# R123X.net
KiCad netlist of a schematic drawn in EAGLE
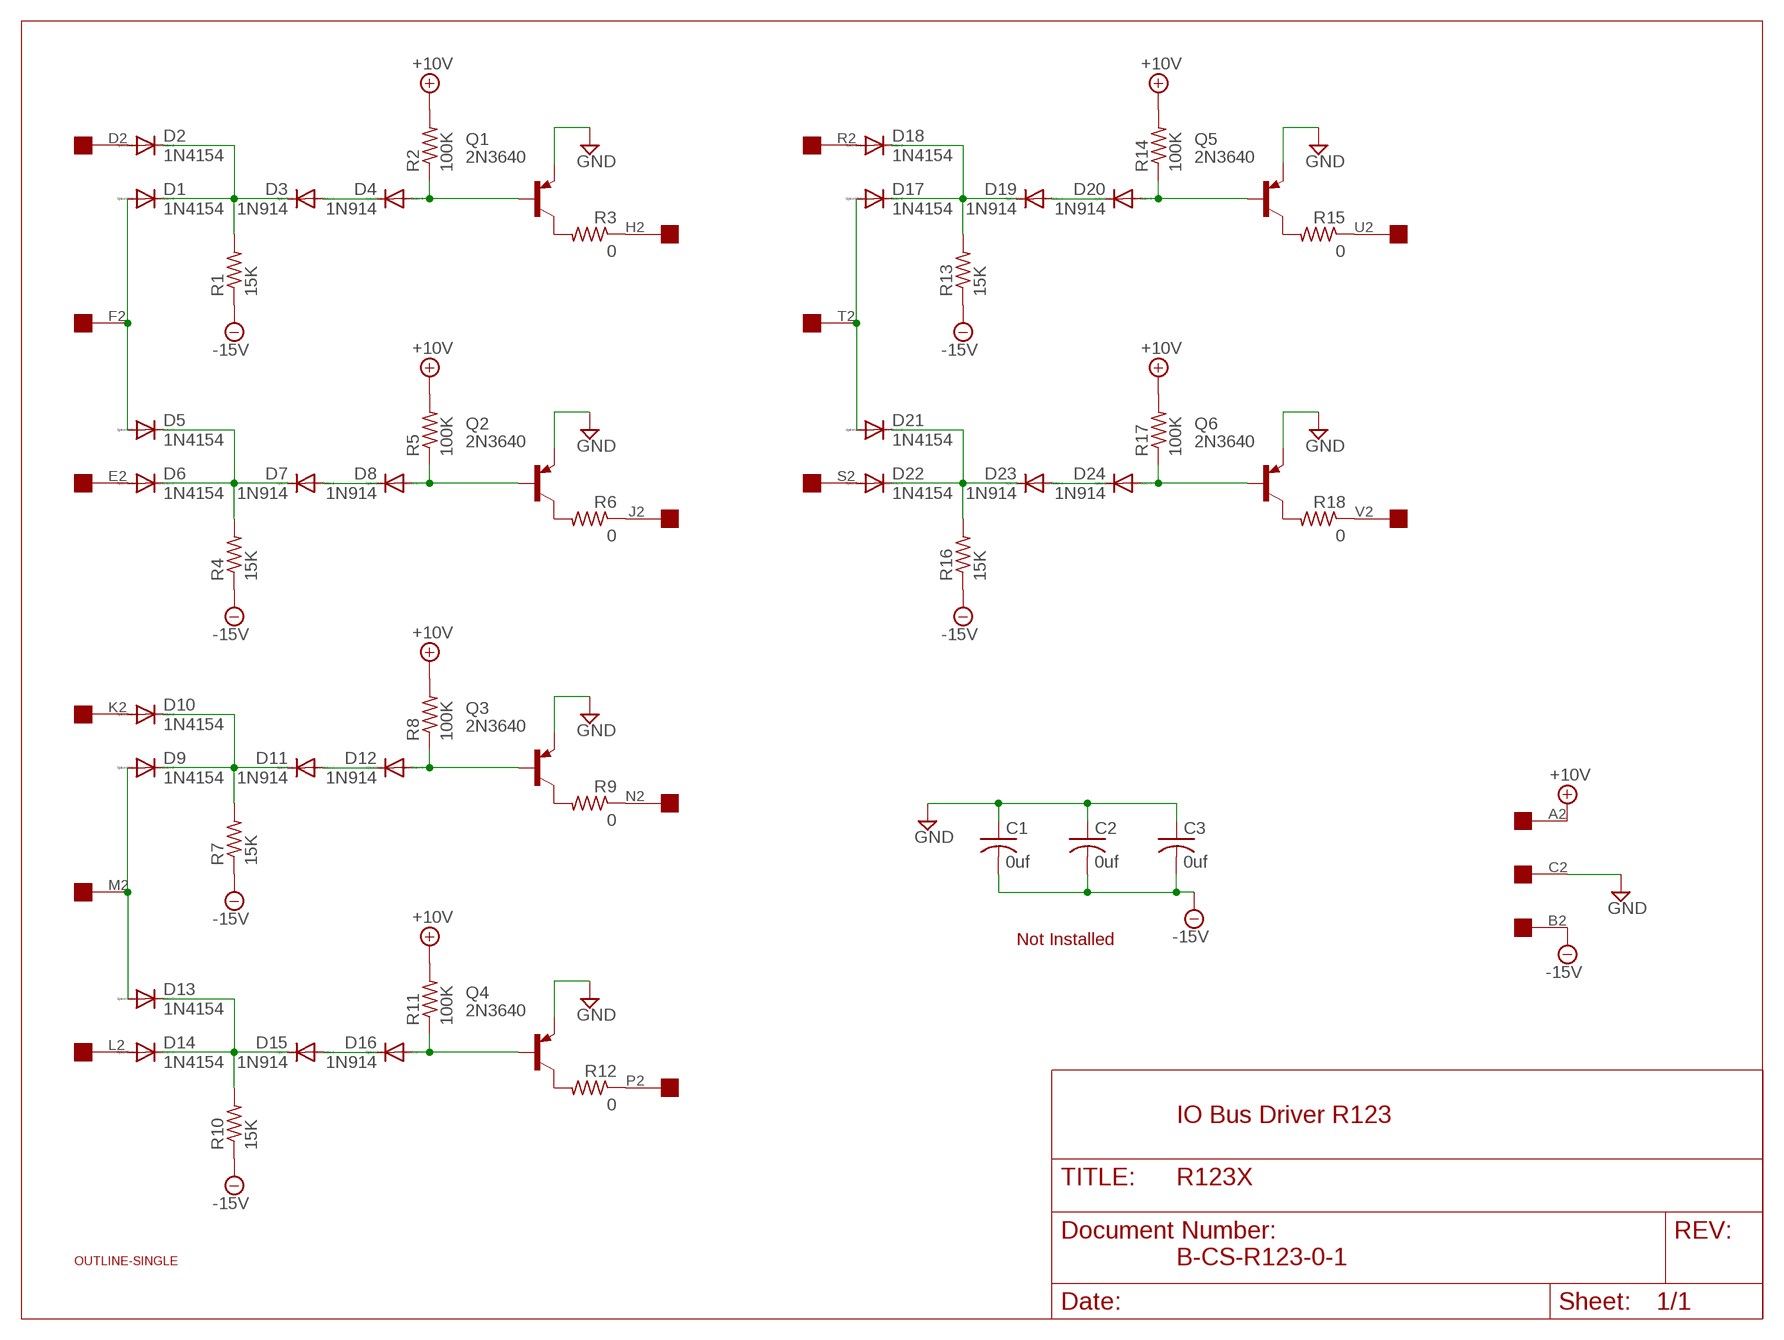
[diagram p0: schematic, sheet 1]

(export (version "E")
  (design (tool "Eeschema 10.0.6"))
  (components
    (comp (ref "C1")
      (value "0uf")
      (footprint "eagle-import:C050-025X075")
      (libsource (lib "eagle-import") (part "C-US050-025X075"))
    )
    (comp (ref "C2")
      (value "0uf")
      (footprint "eagle-import:C050-025X075")
      (libsource (lib "eagle-import") (part "C-US050-025X075"))
    )
    (comp (ref "C3")
      (value "0uf")
      (footprint "eagle-import:C050-025X075")
      (libsource (lib "eagle-import") (part "C-US050-025X075"))
    )
    (comp (ref "D1")
      (value "1N4154")
      (footprint "eagle-import:DO35-10")
      (libsource (lib "eagle-import") (part "1N4148DO35-10"))
    )
    (comp (ref "D2")
      (value "1N4154")
      (footprint "eagle-import:DO35-10")
      (libsource (lib "eagle-import") (part "1N4148DO35-10"))
    )
    (comp (ref "D3")
      (value "1N914")
      (footprint "eagle-import:DO35-10")
      (libsource (lib "eagle-import") (part "1N4148DO35-10"))
    )
    (comp (ref "D4")
      (value "1N914")
      (footprint "eagle-import:DO35-10")
      (libsource (lib "eagle-import") (part "1N4148DO35-10"))
    )
    (comp (ref "D5")
      (value "1N4154")
      (footprint "eagle-import:DO35-10")
      (libsource (lib "eagle-import") (part "1N4148DO35-10"))
    )
    (comp (ref "D6")
      (value "1N4154")
      (footprint "eagle-import:DO35-10")
      (libsource (lib "eagle-import") (part "1N4148DO35-10"))
    )
    (comp (ref "D7")
      (value "1N914")
      (footprint "eagle-import:DO35-10")
      (libsource (lib "eagle-import") (part "1N4148DO35-10"))
    )
    (comp (ref "D8")
      (value "1N914")
      (footprint "eagle-import:DO35-10")
      (libsource (lib "eagle-import") (part "1N4148DO35-10"))
    )
    (comp (ref "D9")
      (value "1N4154")
      (footprint "eagle-import:DO35-10")
      (libsource (lib "eagle-import") (part "1N4148DO35-10"))
    )
    (comp (ref "D10")
      (value "1N4154")
      (footprint "eagle-import:DO35-10")
      (libsource (lib "eagle-import") (part "1N4148DO35-10"))
    )
    (comp (ref "D11")
      (value "1N914")
      (footprint "eagle-import:DO35-10")
      (libsource (lib "eagle-import") (part "1N4148DO35-10"))
    )
    (comp (ref "D12")
      (value "1N914")
      (footprint "eagle-import:DO35-10")
      (libsource (lib "eagle-import") (part "1N4148DO35-10"))
    )
    (comp (ref "D13")
      (value "1N4154")
      (footprint "eagle-import:DO35-10")
      (libsource (lib "eagle-import") (part "1N4148DO35-10"))
    )
    (comp (ref "D14")
      (value "1N4154")
      (footprint "eagle-import:DO35-10")
      (libsource (lib "eagle-import") (part "1N4148DO35-10"))
    )
    (comp (ref "D15")
      (value "1N914")
      (footprint "eagle-import:DO35-10")
      (libsource (lib "eagle-import") (part "1N4148DO35-10"))
    )
    (comp (ref "D16")
      (value "1N914")
      (footprint "eagle-import:DO35-10")
      (libsource (lib "eagle-import") (part "1N4148DO35-10"))
    )
    (comp (ref "D17")
      (value "1N4154")
      (footprint "eagle-import:DO35-10")
      (libsource (lib "eagle-import") (part "1N4148DO35-10"))
    )
    (comp (ref "D18")
      (value "1N4154")
      (footprint "eagle-import:DO35-10")
      (libsource (lib "eagle-import") (part "1N4148DO35-10"))
    )
    (comp (ref "D19")
      (value "1N914")
      (footprint "eagle-import:DO35-10")
      (libsource (lib "eagle-import") (part "1N4148DO35-10"))
    )
    (comp (ref "D20")
      (value "1N914")
      (footprint "eagle-import:DO35-10")
      (libsource (lib "eagle-import") (part "1N4148DO35-10"))
    )
    (comp (ref "D21")
      (value "1N4154")
      (footprint "eagle-import:DO35-10")
      (libsource (lib "eagle-import") (part "1N4148DO35-10"))
    )
    (comp (ref "D22")
      (value "1N4154")
      (footprint "eagle-import:DO35-10")
      (libsource (lib "eagle-import") (part "1N4148DO35-10"))
    )
    (comp (ref "D23")
      (value "1N914")
      (footprint "eagle-import:DO35-10")
      (libsource (lib "eagle-import") (part "1N4148DO35-10"))
    )
    (comp (ref "D24")
      (value "1N914")
      (footprint "eagle-import:DO35-10")
      (libsource (lib "eagle-import") (part "1N4148DO35-10"))
    )
    (comp (ref "Q1")
      (value "2N3640")
      (footprint "eagle-import:TO39")
      (libsource (lib "eagle-import") (part "2N3637"))
    )
    (comp (ref "Q2")
      (value "2N3640")
      (footprint "eagle-import:TO39")
      (libsource (lib "eagle-import") (part "2N3637"))
    )
    (comp (ref "Q3")
      (value "2N3640")
      (footprint "eagle-import:TO39")
      (libsource (lib "eagle-import") (part "2N3637"))
    )
    (comp (ref "Q4")
      (value "2N3640")
      (footprint "eagle-import:TO39")
      (libsource (lib "eagle-import") (part "2N3637"))
    )
    (comp (ref "Q5")
      (value "2N3640")
      (footprint "eagle-import:TO39")
      (libsource (lib "eagle-import") (part "2N3637"))
    )
    (comp (ref "Q6")
      (value "2N3640")
      (footprint "eagle-import:TO39")
      (libsource (lib "eagle-import") (part "2N3637"))
    )
    (comp (ref "R1")
      (value "15K")
      (footprint "eagle-import:0207_10")
      (libsource (lib "eagle-import") (part "R-US_0207/10"))
    )
    (comp (ref "R2")
      (value "100K")
      (footprint "eagle-import:0207_10")
      (libsource (lib "eagle-import") (part "R-US_0207/10"))
    )
    (comp (ref "R3")
      (value "0")
      (footprint "eagle-import:0207_10")
      (libsource (lib "eagle-import") (part "R-US_0207/10"))
    )
    (comp (ref "R4")
      (value "15K")
      (footprint "eagle-import:0207_10")
      (libsource (lib "eagle-import") (part "R-US_0207/10"))
    )
    (comp (ref "R5")
      (value "100K")
      (footprint "eagle-import:0207_10")
      (libsource (lib "eagle-import") (part "R-US_0207/10"))
    )
    (comp (ref "R6")
      (value "0")
      (footprint "eagle-import:0207_10")
      (libsource (lib "eagle-import") (part "R-US_0207/10"))
    )
    (comp (ref "R7")
      (value "15K")
      (footprint "eagle-import:0207_10")
      (libsource (lib "eagle-import") (part "R-US_0207/10"))
    )
    (comp (ref "R8")
      (value "100K")
      (footprint "eagle-import:0207_10")
      (libsource (lib "eagle-import") (part "R-US_0207/10"))
    )
    (comp (ref "R9")
      (value "0")
      (footprint "eagle-import:0207_10")
      (libsource (lib "eagle-import") (part "R-US_0207/10"))
    )
    (comp (ref "R10")
      (value "15K")
      (footprint "eagle-import:0207_10")
      (libsource (lib "eagle-import") (part "R-US_0207/10"))
    )
    (comp (ref "R11")
      (value "100K")
      (footprint "eagle-import:0207_10")
      (libsource (lib "eagle-import") (part "R-US_0207/10"))
    )
    (comp (ref "R12")
      (value "0")
      (footprint "eagle-import:0207_10")
      (libsource (lib "eagle-import") (part "R-US_0207/10"))
    )
    (comp (ref "R13")
      (value "15K")
      (footprint "eagle-import:0207_10")
      (libsource (lib "eagle-import") (part "R-US_0207/10"))
    )
    (comp (ref "R14")
      (value "100K")
      (footprint "eagle-import:0207_10")
      (libsource (lib "eagle-import") (part "R-US_0207/10"))
    )
    (comp (ref "R15")
      (value "0")
      (footprint "eagle-import:0207_10")
      (libsource (lib "eagle-import") (part "R-US_0207/10"))
    )
    (comp (ref "R16")
      (value "15K")
      (footprint "eagle-import:0207_10")
      (libsource (lib "eagle-import") (part "R-US_0207/10"))
    )
    (comp (ref "R17")
      (value "100K")
      (footprint "eagle-import:0207_10")
      (libsource (lib "eagle-import") (part "R-US_0207/10"))
    )
    (comp (ref "R18")
      (value "0")
      (footprint "eagle-import:0207_10")
      (libsource (lib "eagle-import") (part "R-US_0207/10"))
    )
    (comp (ref "U$1")
      (value "OUTLINE-SINGLE")
      (footprint "eagle-import:SINGLE")
      (libsource (lib "eagle-import") (part "OUTLINE-SINGLE"))
    )
    (comp (ref "U$2")
      (value "EDGE-1")
      (footprint "eagle-import:EDGE-CON1")
      (libsource (lib "eagle-import") (part "EDGE-1"))
    )
  )
  (nets
    (net (code "1") (name "+10V") (class "Default")
      (node (ref "R11") (pin "2") (pinfunction "2_2") (pintype "passive"))
      (node (ref "R14") (pin "2") (pinfunction "2_2") (pintype "passive"))
      (node (ref "R17") (pin "2") (pinfunction "2_2") (pintype "passive"))
      (node (ref "R2") (pin "2") (pinfunction "2_2") (pintype "passive"))
      (node (ref "R5") (pin "2") (pinfunction "2_2") (pintype "passive"))
      (node (ref "R8") (pin "2") (pinfunction "2_2") (pintype "passive"))
      (node (ref "U$2") (pin "A2") (pinfunction "1_A2") (pintype "bidirectional"))
    )
    (net (code "2") (name "-15V") (class "Default")
      (node (ref "C1") (pin "2") (pinfunction "2_2") (pintype "passive"))
      (node (ref "C2") (pin "2") (pinfunction "2_2") (pintype "passive"))
      (node (ref "C3") (pin "2") (pinfunction "2_2") (pintype "passive"))
      (node (ref "R1") (pin "1") (pinfunction "1_1") (pintype "passive"))
      (node (ref "R10") (pin "1") (pinfunction "1_1") (pintype "passive"))
      (node (ref "R13") (pin "1") (pinfunction "1_1") (pintype "passive"))
      (node (ref "R16") (pin "1") (pinfunction "1_1") (pintype "passive"))
      (node (ref "R4") (pin "1") (pinfunction "1_1") (pintype "passive"))
      (node (ref "R7") (pin "1") (pinfunction "1_1") (pintype "passive"))
      (node (ref "U$2") (pin "B2") (pinfunction "1_B2") (pintype "bidirectional"))
    )
    (net (code "3") (name "GND") (class "Default")
      (node (ref "C1") (pin "1") (pinfunction "1_1") (pintype "passive"))
      (node (ref "C2") (pin "1") (pinfunction "1_1") (pintype "passive"))
      (node (ref "C3") (pin "1") (pinfunction "1_1") (pintype "passive"))
      (node (ref "Q1") (pin "1") (pinfunction "E_1") (pintype "passive"))
      (node (ref "Q2") (pin "1") (pinfunction "E_1") (pintype "passive"))
      (node (ref "Q3") (pin "1") (pinfunction "E_1") (pintype "passive"))
      (node (ref "Q4") (pin "1") (pinfunction "E_1") (pintype "passive"))
      (node (ref "Q5") (pin "1") (pinfunction "E_1") (pintype "passive"))
      (node (ref "Q6") (pin "1") (pinfunction "E_1") (pintype "passive"))
      (node (ref "U$2") (pin "C2") (pinfunction "1_C2") (pintype "bidirectional"))
    )
    (net (code "4") (name "Net-(D1-PadC)") (class "Default")
      (node (ref "D1") (pin "C") (pinfunction "C_C") (pintype "passive"))
      (node (ref "D2") (pin "C") (pinfunction "C_C") (pintype "passive"))
      (node (ref "D3") (pin "C") (pinfunction "C_C") (pintype "passive"))
      (node (ref "R1") (pin "2") (pinfunction "2_2") (pintype "passive"))
    )
    (net (code "5") (name "Net-(D3-PadA)") (class "Default")
      (node (ref "D3") (pin "A") (pinfunction "A_A") (pintype "passive"))
      (node (ref "D4") (pin "C") (pinfunction "C_C") (pintype "passive"))
    )
    (net (code "6") (name "Net-(D5-PadC)") (class "Default")
      (node (ref "D5") (pin "C") (pinfunction "C_C") (pintype "passive"))
      (node (ref "D6") (pin "C") (pinfunction "C_C") (pintype "passive"))
      (node (ref "D7") (pin "C") (pinfunction "C_C") (pintype "passive"))
      (node (ref "R4") (pin "2") (pinfunction "2_2") (pintype "passive"))
    )
    (net (code "7") (name "Net-(D7-PadA)") (class "Default")
      (node (ref "D7") (pin "A") (pinfunction "A_A") (pintype "passive"))
      (node (ref "D8") (pin "C") (pinfunction "C_C") (pintype "passive"))
    )
    (net (code "8") (name "Net-(D10-PadC)") (class "Default")
      (node (ref "D10") (pin "C") (pinfunction "C_C") (pintype "passive"))
      (node (ref "D11") (pin "C") (pinfunction "C_C") (pintype "passive"))
      (node (ref "D9") (pin "C") (pinfunction "C_C") (pintype "passive"))
      (node (ref "R7") (pin "2") (pinfunction "2_2") (pintype "passive"))
    )
    (net (code "9") (name "Net-(D11-PadA)") (class "Default")
      (node (ref "D11") (pin "A") (pinfunction "A_A") (pintype "passive"))
      (node (ref "D12") (pin "C") (pinfunction "C_C") (pintype "passive"))
    )
    (net (code "10") (name "Net-(D13-PadC)") (class "Default")
      (node (ref "D13") (pin "C") (pinfunction "C_C") (pintype "passive"))
      (node (ref "D14") (pin "C") (pinfunction "C_C") (pintype "passive"))
      (node (ref "D15") (pin "C") (pinfunction "C_C") (pintype "passive"))
      (node (ref "R10") (pin "2") (pinfunction "2_2") (pintype "passive"))
    )
    (net (code "11") (name "Net-(D15-PadA)") (class "Default")
      (node (ref "D15") (pin "A") (pinfunction "A_A") (pintype "passive"))
      (node (ref "D16") (pin "C") (pinfunction "C_C") (pintype "passive"))
    )
    (net (code "12") (name "Net-(D17-PadC)") (class "Default")
      (node (ref "D17") (pin "C") (pinfunction "C_C") (pintype "passive"))
      (node (ref "D18") (pin "C") (pinfunction "C_C") (pintype "passive"))
      (node (ref "D19") (pin "C") (pinfunction "C_C") (pintype "passive"))
      (node (ref "R13") (pin "2") (pinfunction "2_2") (pintype "passive"))
    )
    (net (code "13") (name "Net-(D19-PadA)") (class "Default")
      (node (ref "D19") (pin "A") (pinfunction "A_A") (pintype "passive"))
      (node (ref "D20") (pin "C") (pinfunction "C_C") (pintype "passive"))
    )
    (net (code "14") (name "Net-(D21-PadC)") (class "Default")
      (node (ref "D21") (pin "C") (pinfunction "C_C") (pintype "passive"))
      (node (ref "D22") (pin "C") (pinfunction "C_C") (pintype "passive"))
      (node (ref "D23") (pin "C") (pinfunction "C_C") (pintype "passive"))
      (node (ref "R16") (pin "2") (pinfunction "2_2") (pintype "passive"))
    )
    (net (code "15") (name "Net-(D23-PadA)") (class "Default")
      (node (ref "D23") (pin "A") (pinfunction "A_A") (pintype "passive"))
      (node (ref "D24") (pin "C") (pinfunction "C_C") (pintype "passive"))
    )
    (net (code "16") (name "Net-(Q1-B)") (class "Default")
      (node (ref "D4") (pin "A") (pinfunction "A_A") (pintype "passive"))
      (node (ref "Q1") (pin "2") (pinfunction "B_2") (pintype "passive"))
      (node (ref "R2") (pin "1") (pinfunction "1_1") (pintype "passive"))
    )
    (net (code "17") (name "Net-(Q1-C)") (class "Default")
      (node (ref "Q1") (pin "3") (pinfunction "C_3") (pintype "passive"))
      (node (ref "R3") (pin "2") (pinfunction "2_2") (pintype "passive"))
    )
    (net (code "18") (name "Net-(Q2-B)") (class "Default")
      (node (ref "D8") (pin "A") (pinfunction "A_A") (pintype "passive"))
      (node (ref "Q2") (pin "2") (pinfunction "B_2") (pintype "passive"))
      (node (ref "R5") (pin "1") (pinfunction "1_1") (pintype "passive"))
    )
    (net (code "19") (name "Net-(Q2-C)") (class "Default")
      (node (ref "Q2") (pin "3") (pinfunction "C_3") (pintype "passive"))
      (node (ref "R6") (pin "2") (pinfunction "2_2") (pintype "passive"))
    )
    (net (code "20") (name "Net-(Q3-B)") (class "Default")
      (node (ref "D12") (pin "A") (pinfunction "A_A") (pintype "passive"))
      (node (ref "Q3") (pin "2") (pinfunction "B_2") (pintype "passive"))
      (node (ref "R8") (pin "1") (pinfunction "1_1") (pintype "passive"))
    )
    (net (code "21") (name "Net-(Q3-C)") (class "Default")
      (node (ref "Q3") (pin "3") (pinfunction "C_3") (pintype "passive"))
      (node (ref "R9") (pin "2") (pinfunction "2_2") (pintype "passive"))
    )
    (net (code "22") (name "Net-(Q4-B)") (class "Default")
      (node (ref "D16") (pin "A") (pinfunction "A_A") (pintype "passive"))
      (node (ref "Q4") (pin "2") (pinfunction "B_2") (pintype "passive"))
      (node (ref "R11") (pin "1") (pinfunction "1_1") (pintype "passive"))
    )
    (net (code "23") (name "Net-(Q4-C)") (class "Default")
      (node (ref "Q4") (pin "3") (pinfunction "C_3") (pintype "passive"))
      (node (ref "R12") (pin "2") (pinfunction "2_2") (pintype "passive"))
    )
    (net (code "24") (name "Net-(Q5-B)") (class "Default")
      (node (ref "D20") (pin "A") (pinfunction "A_A") (pintype "passive"))
      (node (ref "Q5") (pin "2") (pinfunction "B_2") (pintype "passive"))
      (node (ref "R14") (pin "1") (pinfunction "1_1") (pintype "passive"))
    )
    (net (code "25") (name "Net-(Q5-C)") (class "Default")
      (node (ref "Q5") (pin "3") (pinfunction "C_3") (pintype "passive"))
      (node (ref "R15") (pin "2") (pinfunction "2_2") (pintype "passive"))
    )
    (net (code "26") (name "Net-(Q6-B)") (class "Default")
      (node (ref "D24") (pin "A") (pinfunction "A_A") (pintype "passive"))
      (node (ref "Q6") (pin "2") (pinfunction "B_2") (pintype "passive"))
      (node (ref "R17") (pin "1") (pinfunction "1_1") (pintype "passive"))
    )
    (net (code "27") (name "Net-(Q6-C)") (class "Default")
      (node (ref "Q6") (pin "3") (pinfunction "C_3") (pintype "passive"))
      (node (ref "R18") (pin "2") (pinfunction "2_2") (pintype "passive"))
    )
    (net (code "28") (name "Net-(U$2D-1)") (class "Default")
      (node (ref "D2") (pin "A") (pinfunction "A_A") (pintype "passive"))
      (node (ref "U$2") (pin "D2") (pinfunction "1_D2") (pintype "bidirectional"))
    )
    (net (code "29") (name "Net-(U$2E-1)") (class "Default")
      (node (ref "D6") (pin "A") (pinfunction "A_A") (pintype "passive"))
      (node (ref "U$2") (pin "E2") (pinfunction "1_E2") (pintype "bidirectional"))
    )
    (net (code "30") (name "Net-(U$2F-1)") (class "Default")
      (node (ref "D1") (pin "A") (pinfunction "A_A") (pintype "passive"))
      (node (ref "D5") (pin "A") (pinfunction "A_A") (pintype "passive"))
      (node (ref "U$2") (pin "F2") (pinfunction "1_F2") (pintype "bidirectional"))
    )
    (net (code "31") (name "Net-(U$2G-1)") (class "Default")
      (node (ref "R3") (pin "1") (pinfunction "1_1") (pintype "passive"))
      (node (ref "U$2") (pin "H2") (pinfunction "1_H2") (pintype "bidirectional"))
    )
    (net (code "32") (name "Net-(U$2H-1)") (class "Default")
      (node (ref "R6") (pin "1") (pinfunction "1_1") (pintype "passive"))
      (node (ref "U$2") (pin "J2") (pinfunction "1_J2") (pintype "bidirectional"))
    )
    (net (code "33") (name "Net-(U$2I-1)") (class "Default")
      (node (ref "D10") (pin "A") (pinfunction "A_A") (pintype "passive"))
      (node (ref "U$2") (pin "K2") (pinfunction "1_K2") (pintype "bidirectional"))
    )
    (net (code "34") (name "Net-(U$2J-1)") (class "Default")
      (node (ref "D14") (pin "A") (pinfunction "A_A") (pintype "passive"))
      (node (ref "U$2") (pin "L2") (pinfunction "1_L2") (pintype "bidirectional"))
    )
    (net (code "35") (name "Net-(U$2K-1)") (class "Default")
      (node (ref "D13") (pin "A") (pinfunction "A_A") (pintype "passive"))
      (node (ref "D9") (pin "A") (pinfunction "A_A") (pintype "passive"))
      (node (ref "U$2") (pin "M2") (pinfunction "1_M2") (pintype "bidirectional"))
    )
    (net (code "36") (name "Net-(U$2L-1)") (class "Default")
      (node (ref "R9") (pin "1") (pinfunction "1_1") (pintype "passive"))
      (node (ref "U$2") (pin "N2") (pinfunction "1_N2") (pintype "bidirectional"))
    )
    (net (code "37") (name "Net-(U$2M-1)") (class "Default")
      (node (ref "R12") (pin "1") (pinfunction "1_1") (pintype "passive"))
      (node (ref "U$2") (pin "P2") (pinfunction "1_P2") (pintype "bidirectional"))
    )
    (net (code "38") (name "Net-(U$2N-1)") (class "Default")
      (node (ref "D18") (pin "A") (pinfunction "A_A") (pintype "passive"))
      (node (ref "U$2") (pin "R2") (pinfunction "1_R2") (pintype "bidirectional"))
    )
    (net (code "39") (name "Net-(U$2O-1)") (class "Default")
      (node (ref "D22") (pin "A") (pinfunction "A_A") (pintype "passive"))
      (node (ref "U$2") (pin "S2") (pinfunction "1_S2") (pintype "bidirectional"))
    )
    (net (code "40") (name "Net-(U$2P-1)") (class "Default")
      (node (ref "D17") (pin "A") (pinfunction "A_A") (pintype "passive"))
      (node (ref "D21") (pin "A") (pinfunction "A_A") (pintype "passive"))
      (node (ref "U$2") (pin "T2") (pinfunction "1_T2") (pintype "bidirectional"))
    )
    (net (code "41") (name "Net-(U$2Q-1)") (class "Default")
      (node (ref "R15") (pin "1") (pinfunction "1_1") (pintype "passive"))
      (node (ref "U$2") (pin "U2") (pinfunction "1_U2") (pintype "bidirectional"))
    )
    (net (code "42") (name "Net-(U$2R-1)") (class "Default")
      (node (ref "R18") (pin "1") (pinfunction "1_1") (pintype "passive"))
      (node (ref "U$2") (pin "V2") (pinfunction "1_V2") (pintype "bidirectional"))
    )
  )
)
